# Overview.net
KiCad netlist of a schematic drawn in Altium Designer
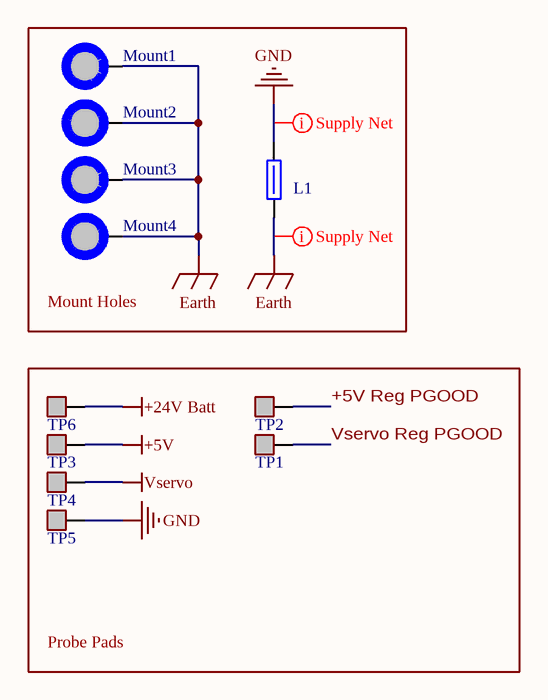
[diagram p0: Overview.SchDoc]

(export (version "E")
  (design (tool "Eeschema 10.0.6"))
  (components
    (comp (ref "L1")
      (value "652-MH2029-300Y")
      (footprint "[Ferrite] SMD Bead 0805 (1)")
      (libsource (lib "RADM Components") (part "[Ferrite] SMD Ferrite Bead (1)"))
    )
    (comp (ref "Mount1")
      (value "M3 Mount Hole")
      (footprint "[Mount] M3 Mount Hole")
      (description "Place at least 4.5mm from board edge. Plated.")
      (libsource (lib "RADM Connectors") (part "[Mount] M3 Mount Hole"))
    )
    (comp (ref "Mount2")
      (value "M3 Mount Hole")
      (footprint "[Mount] M3 Mount Hole")
      (description "Place at least 4.5mm from board edge. Plated.")
      (libsource (lib "RADM Connectors") (part "[Mount] M3 Mount Hole"))
    )
    (comp (ref "Mount3")
      (value "M3 Mount Hole")
      (footprint "[Mount] M3 Mount Hole")
      (description "Place at least 4.5mm from board edge. Plated.")
      (libsource (lib "RADM Connectors") (part "[Mount] M3 Mount Hole"))
    )
    (comp (ref "Mount4")
      (value "M3 Mount Hole")
      (footprint "[Mount] M3 Mount Hole")
      (description "Place at least 4.5mm from board edge. Plated.")
      (libsource (lib "RADM Connectors") (part "[Mount] M3 Mount Hole"))
    )
    (comp (ref "TP1")
      (value "Probe Pad")
      (footprint "[Probe] Touch Pad")
      (libsource (lib "RADM Connectors") (part "[Probe] Touch Pad"))
    )
    (comp (ref "TP2")
      (value "Probe Pad")
      (footprint "[Probe] Touch Pad")
      (libsource (lib "RADM Connectors") (part "[Probe] Touch Pad"))
    )
    (comp (ref "TP3")
      (value "Probe Pad")
      (footprint "[Probe] Touch Pad")
      (libsource (lib "RADM Connectors") (part "[Probe] Touch Pad"))
    )
    (comp (ref "TP4")
      (value "Probe Pad")
      (footprint "[Probe] Touch Pad")
      (libsource (lib "RADM Connectors") (part "[Probe] Touch Pad"))
    )
    (comp (ref "TP5")
      (value "Probe Pad")
      (footprint "[Probe] Touch Pad")
      (libsource (lib "RADM Connectors") (part "[Probe] Touch Pad"))
    )
    (comp (ref "TP6")
      (value "Probe Pad")
      (footprint "[Probe] Touch Pad")
      (libsource (lib "RADM Connectors") (part "[Probe] Touch Pad"))
    )
  )
  (nets
    (net (code "1") (name "+5V") (class "Default")
      (node (ref "TP3") (pin "1") (pinfunction "1_1") (pintype "passive"))
    )
    (net (code "2") (name "+24V Batt") (class "Default")
      (node (ref "TP6") (pin "1") (pinfunction "1_1") (pintype "passive"))
    )
    (net (code "3") (name "/+5V Reg PGOOD") (class "Default")
      (node (ref "TP2") (pin "1") (pinfunction "1_1") (pintype "passive"))
    )
    (net (code "4") (name "/Vservo Reg PGOOD") (class "Default")
      (node (ref "TP1") (pin "1") (pinfunction "1_1") (pintype "passive"))
    )
    (net (code "5") (name "Earth") (class "Default")
      (node (ref "L1") (pin "1") (pinfunction "1_1") (pintype "passive"))
      (node (ref "Mount1") (pin "1") (pintype "power_in"))
      (node (ref "Mount2") (pin "1") (pintype "power_in"))
      (node (ref "Mount3") (pin "1") (pintype "power_in"))
      (node (ref "Mount4") (pin "1") (pintype "power_in"))
    )
    (net (code "6") (name "GND") (class "Default")
      (node (ref "L1") (pin "2") (pinfunction "2_2") (pintype "passive"))
      (node (ref "TP5") (pin "1") (pinfunction "1_1") (pintype "passive"))
    )
    (net (code "7") (name "Vservo") (class "Default")
      (node (ref "TP4") (pin "1") (pinfunction "1_1") (pintype "passive"))
    )
  )
)
